# Tacile-Buttons.net
KiCad netlist of a schematic drawn in Altium Designer
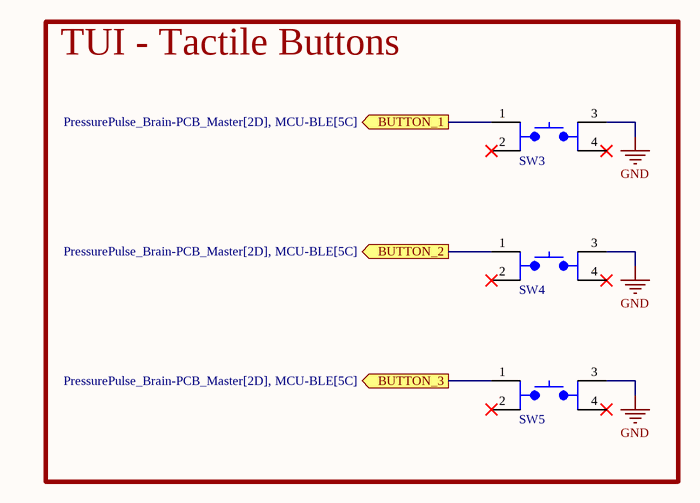
[diagram p0: Tacile-Buttons.SchDoc]

(export (version "E")
  (design (tool "Eeschema 10.0.6"))
  (components
    (comp (ref "SW3")
      (value "SPDT SMT Tactile Push Button Switch")
      (footprint "PressurePulse:TL6200")
      (libsource (lib "PressurePulse") (part "SPDT SMT Tactile Push Button Switch"))
    )
    (comp (ref "SW4")
      (value "SPDT SMT Tactile Push Button Switch")
      (footprint "PressurePulse:TL6200")
      (libsource (lib "PressurePulse") (part "SPDT SMT Tactile Push Button Switch"))
    )
    (comp (ref "SW5")
      (value "SPDT SMT Tactile Push Button Switch")
      (footprint "PressurePulse:TL6200")
      (libsource (lib "PressurePulse") (part "SPDT SMT Tactile Push Button Switch"))
    )
  )
  (nets
    (net (code "1") (name "/BUTTON_1") (class "Default")
      (node (ref "SW3") (pin "1") (pinfunction "1_1") (pintype "passive"))
    )
    (net (code "2") (name "/BUTTON_2") (class "Default")
      (node (ref "SW4") (pin "1") (pinfunction "1_1") (pintype "passive"))
    )
    (net (code "3") (name "/BUTTON_3") (class "Default")
      (node (ref "SW5") (pin "1") (pinfunction "1_1") (pintype "passive"))
    )
    (net (code "4") (name "GND") (class "Default")
      (node (ref "SW3") (pin "3") (pinfunction "3_3") (pintype "passive"))
      (node (ref "SW4") (pin "3") (pinfunction "3_3") (pintype "passive"))
      (node (ref "SW5") (pin "3") (pinfunction "3_3") (pintype "passive"))
    )
    (net (code "5") (name "unconnected-(SW3-Pad2)") (class "Default")
      (node (ref "SW3") (pin "2") (pinfunction "2_2") (pintype "passive+no_connect"))
    )
    (net (code "6") (name "unconnected-(SW3-Pad4)") (class "Default")
      (node (ref "SW3") (pin "4") (pinfunction "4_4") (pintype "passive+no_connect"))
    )
    (net (code "7") (name "unconnected-(SW4-Pad2)") (class "Default")
      (node (ref "SW4") (pin "2") (pinfunction "2_2") (pintype "passive+no_connect"))
    )
    (net (code "8") (name "unconnected-(SW4-Pad4)") (class "Default")
      (node (ref "SW4") (pin "4") (pinfunction "4_4") (pintype "passive+no_connect"))
    )
    (net (code "9") (name "unconnected-(SW5-Pad2)") (class "Default")
      (node (ref "SW5") (pin "2") (pinfunction "2_2") (pintype "passive+no_connect"))
    )
    (net (code "10") (name "unconnected-(SW5-Pad4)") (class "Default")
      (node (ref "SW5") (pin "4") (pinfunction "4_4") (pintype "passive+no_connect"))
    )
  )
)
